# periph-tester.net
KiCad netlist of a schematic drawn in EAGLE
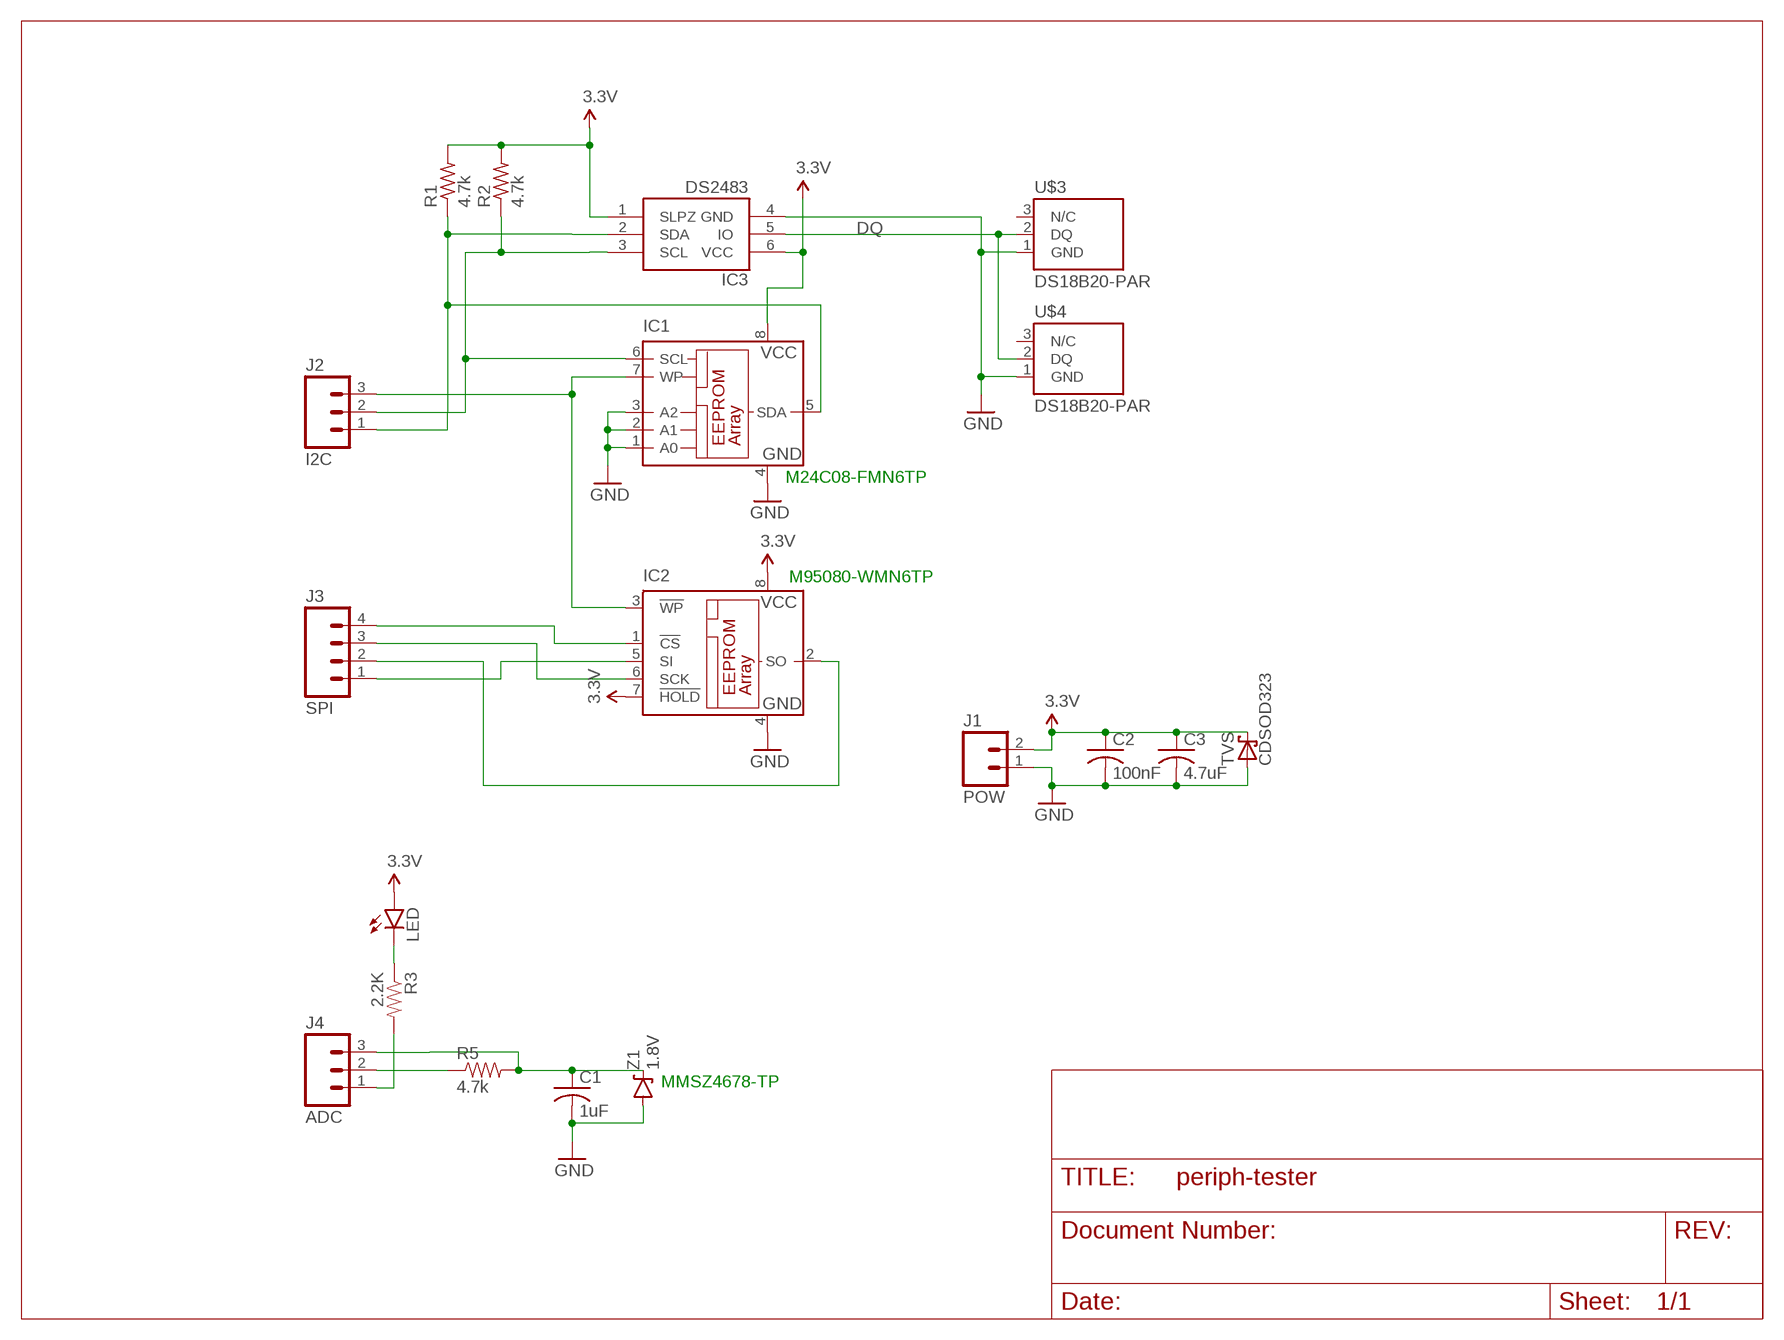
[diagram p0: schematic, sheet 1]

(export (version "E")
  (design (tool "Eeschema 10.0.6"))
  (components
    (comp (ref "C1")
      (value "1uF")
      (footprint "eagle-import:C0603K")
      (libsource (lib "eagle-import") (part "C-USC0603K"))
    )
    (comp (ref "C2")
      (value "100nF")
      (footprint "eagle-import:C0603K")
      (libsource (lib "eagle-import") (part "C-USC0603K"))
    )
    (comp (ref "C3")
      (value "4.7uF")
      (footprint "eagle-import:C0805K")
      (libsource (lib "eagle-import") (part "C-USC0805K"))
    )
    (comp (ref "IC1")
      (value "24C04SN")
      (footprint "eagle-import:SO-08")
      (fields (field (name "MPN") "M24C04-WMN6P"))
      (libsource (lib "eagle-import") (part "24CSN04"))
    )
    (comp (ref "IC2")
      (value "25C080SN")
      (footprint "eagle-import:SO-08")
      (fields (field (name "MF") "MICROCHIP") (field (name "MPN") "25C080/SN"))
      (libsource (lib "eagle-import") (part "25SNC080"))
    )
    (comp (ref "IC3")
      (value "DS2483")
      (footprint "eagle-import:SOT23-6")
      (libsource (lib "eagle-import") (part "DS2483"))
    )
    (comp (ref "J1")
      (value "POW")
      (footprint "eagle-import:1X02")
      (libsource (lib "eagle-import") (part "M02PTH"))
    )
    (comp (ref "J2")
      (value "I2C")
      (footprint "eagle-import:1X03")
      (libsource (lib "eagle-import") (part "M03PTH"))
    )
    (comp (ref "J3")
      (value "SPI")
      (footprint "eagle-import:1X04")
      (libsource (lib "eagle-import") (part "M04PTH"))
    )
    (comp (ref "J4")
      (value "ADC")
      (footprint "eagle-import:1X03")
      (libsource (lib "eagle-import") (part "M03PTH"))
    )
    (comp (ref "LED")
      (value "LED0603")
      (footprint "eagle-import:LED-0603")
      (libsource (lib "eagle-import") (part "LED0603"))
    )
    (comp (ref "R1")
      (value "4.7k")
      (footprint "eagle-import:R0603")
      (libsource (lib "eagle-import") (part "R-US_R0603"))
    )
    (comp (ref "R2")
      (value "4.7k")
      (footprint "eagle-import:R0603")
      (libsource (lib "eagle-import") (part "R-US_R0603"))
    )
    (comp (ref "R3")
      (value "2.2K")
      (footprint "eagle-import:0603-RES")
      (libsource (lib "eagle-import") (part "RESISTOR0603-RES"))
    )
    (comp (ref "R5")
      (value "4.7k")
      (footprint "eagle-import:0603-RES")
      (libsource (lib "eagle-import") (part "RESISTOR0603-RES"))
    )
    (comp (ref "TVS")
      (value "CDSOD323")
      (footprint "eagle-import:SOD323-W")
      (libsource (lib "eagle-import") (part "CDSOD323"))
    )
    (comp (ref "U$3")
      (value "DS18B20-PAR")
      (footprint "eagle-import:TO-92")
      (libsource (lib "eagle-import") (part "DS18B20-PAR"))
    )
    (comp (ref "U$4")
      (value "DS18B20-PAR")
      (footprint "eagle-import:TO-92")
      (libsource (lib "eagle-import") (part "DS18B20-PAR"))
    )
    (comp (ref "Z1")
      (value "1.8V")
      (footprint "eagle-import:SOD-123")
      (libsource (lib "eagle-import") (part "DIODE-ZENER16V"))
    )
  )
  (nets
    (net (code "1") (name "/DQ") (class "Default")
      (node (ref "IC3") (pin "5") (pinfunction "IO_5") (pintype "bidirectional"))
      (node (ref "U$3") (pin "2") (pinfunction "DQ_2") (pintype "bidirectional"))
      (node (ref "U$4") (pin "2") (pinfunction "DQ_2") (pintype "bidirectional"))
    )
    (net (code "2") (name "3.3V") (class "Default")
      (node (ref "C2") (pin "1") (pinfunction "1_1") (pintype "passive"))
      (node (ref "C3") (pin "1") (pinfunction "1_1") (pintype "passive"))
      (node (ref "IC1") (pin "8") (pinfunction "VCC_8") (pintype "power_in"))
      (node (ref "IC2") (pin "7") (pinfunction "~{HOLD}_7") (pintype "input"))
      (node (ref "IC2") (pin "8") (pinfunction "VCC_8") (pintype "power_in"))
      (node (ref "IC3") (pin "1") (pinfunction "SLPZ_1") (pintype "bidirectional"))
      (node (ref "IC3") (pin "6") (pinfunction "VCC_6") (pintype "bidirectional"))
      (node (ref "J1") (pin "2") (pinfunction "2_2") (pintype "passive"))
      (node (ref "LED") (pin "A") (pinfunction "A_A") (pintype "passive"))
      (node (ref "R1") (pin "2") (pinfunction "2_2") (pintype "passive"))
      (node (ref "R2") (pin "2") (pinfunction "2_2") (pintype "passive"))
      (node (ref "TVS") (pin "C") (pinfunction "C_C") (pintype "passive"))
    )
    (net (code "3") (name "GND") (class "Default")
      (node (ref "C1") (pin "2") (pinfunction "2_2") (pintype "passive"))
      (node (ref "C2") (pin "2") (pinfunction "2_2") (pintype "passive"))
      (node (ref "C3") (pin "2") (pinfunction "2_2") (pintype "passive"))
      (node (ref "IC1") (pin "1") (pinfunction "A0_1") (pintype "input"))
      (node (ref "IC1") (pin "2") (pinfunction "A1_2") (pintype "input"))
      (node (ref "IC1") (pin "3") (pinfunction "A2_3") (pintype "input"))
      (node (ref "IC1") (pin "4") (pinfunction "GND_4") (pintype "power_in"))
      (node (ref "IC2") (pin "4") (pinfunction "GND_4") (pintype "power_in"))
      (node (ref "IC3") (pin "4") (pinfunction "GND_4") (pintype "bidirectional"))
      (node (ref "J1") (pin "1") (pinfunction "1_1") (pintype "passive"))
      (node (ref "TVS") (pin "A") (pinfunction "A_A") (pintype "passive"))
      (node (ref "U$3") (pin "1") (pinfunction "GND_1") (pintype "power_in"))
      (node (ref "U$4") (pin "1") (pinfunction "GND_1") (pintype "power_in"))
      (node (ref "Z1") (pin "A") (pinfunction "A_A") (pintype "passive"))
    )
    (net (code "4") (name "Net-(C1-Pad1)") (class "Default")
      (node (ref "C1") (pin "1") (pinfunction "1_1") (pintype "passive"))
      (node (ref "J4") (pin "3") (pinfunction "3_3") (pintype "passive"))
      (node (ref "R5") (pin "2") (pinfunction "2_2") (pintype "passive"))
      (node (ref "Z1") (pin "C") (pinfunction "C_C") (pintype "passive"))
    )
    (net (code "5") (name "Net-(IC1-SCL)") (class "Default")
      (node (ref "IC1") (pin "6") (pinfunction "SCL_6") (pintype "input"))
      (node (ref "IC3") (pin "3") (pinfunction "SCL_3") (pintype "bidirectional"))
      (node (ref "J2") (pin "2") (pinfunction "2_2") (pintype "passive"))
      (node (ref "R2") (pin "1") (pinfunction "1_1") (pintype "passive"))
    )
    (net (code "6") (name "Net-(IC1-SDA)") (class "Default")
      (node (ref "IC1") (pin "5") (pinfunction "SDA_5") (pintype "bidirectional"))
      (node (ref "IC3") (pin "2") (pinfunction "SDA_2") (pintype "bidirectional"))
      (node (ref "J2") (pin "1") (pinfunction "1_1") (pintype "passive"))
      (node (ref "R1") (pin "1") (pinfunction "1_1") (pintype "passive"))
    )
    (net (code "7") (name "Net-(IC1-WP)") (class "Default")
      (node (ref "IC1") (pin "7") (pinfunction "WP_7") (pintype "input"))
      (node (ref "IC2") (pin "3") (pinfunction "~{WP}_3") (pintype "input"))
      (node (ref "J2") (pin "3") (pinfunction "3_3") (pintype "passive"))
    )
    (net (code "8") (name "Net-(IC2-SCK)") (class "Default")
      (node (ref "IC2") (pin "6") (pinfunction "SCK_6") (pintype "input"))
      (node (ref "J3") (pin "3") (pinfunction "3_3") (pintype "passive"))
    )
    (net (code "9") (name "Net-(IC2-SI)") (class "Default")
      (node (ref "IC2") (pin "5") (pinfunction "SI_5") (pintype "input"))
      (node (ref "J3") (pin "1") (pinfunction "1_1") (pintype "passive"))
    )
    (net (code "10") (name "Net-(IC2-SO)") (class "Default")
      (node (ref "IC2") (pin "2") (pinfunction "SO_2") (pintype "bidirectional"))
      (node (ref "J3") (pin "2") (pinfunction "2_2") (pintype "passive"))
    )
    (net (code "11") (name "Net-(IC2-~{CS})") (class "Default")
      (node (ref "IC2") (pin "1") (pinfunction "~{CS}_1") (pintype "input"))
      (node (ref "J3") (pin "4") (pinfunction "4_4") (pintype "passive"))
    )
    (net (code "12") (name "Net-(J4-Pad1)") (class "Default")
      (node (ref "J4") (pin "1") (pinfunction "1_1") (pintype "passive"))
      (node (ref "R3") (pin "2") (pinfunction "2_2") (pintype "passive"))
    )
    (net (code "13") (name "Net-(J4-Pad2)") (class "Default")
      (node (ref "J4") (pin "2") (pinfunction "2_2") (pintype "passive"))
      (node (ref "R5") (pin "1") (pinfunction "1_1") (pintype "passive"))
    )
    (net (code "14") (name "Net-(LED-PadC)") (class "Default")
      (node (ref "LED") (pin "C") (pinfunction "C_C") (pintype "passive"))
      (node (ref "R3") (pin "1") (pinfunction "1_1") (pintype "passive"))
    )
    (net (code "15") (name "unconnected-(U$3-N{slash}C-Pad3)") (class "Default")
      (node (ref "U$3") (pin "3") (pinfunction "N/C_3") (pintype "bidirectional"))
    )
    (net (code "16") (name "unconnected-(U$4-N{slash}C-Pad3)") (class "Default")
      (node (ref "U$4") (pin "3") (pinfunction "N/C_3") (pintype "bidirectional"))
    )
  )
)
